# esp12e.net
KiCad netlist of a schematic drawn in EAGLE
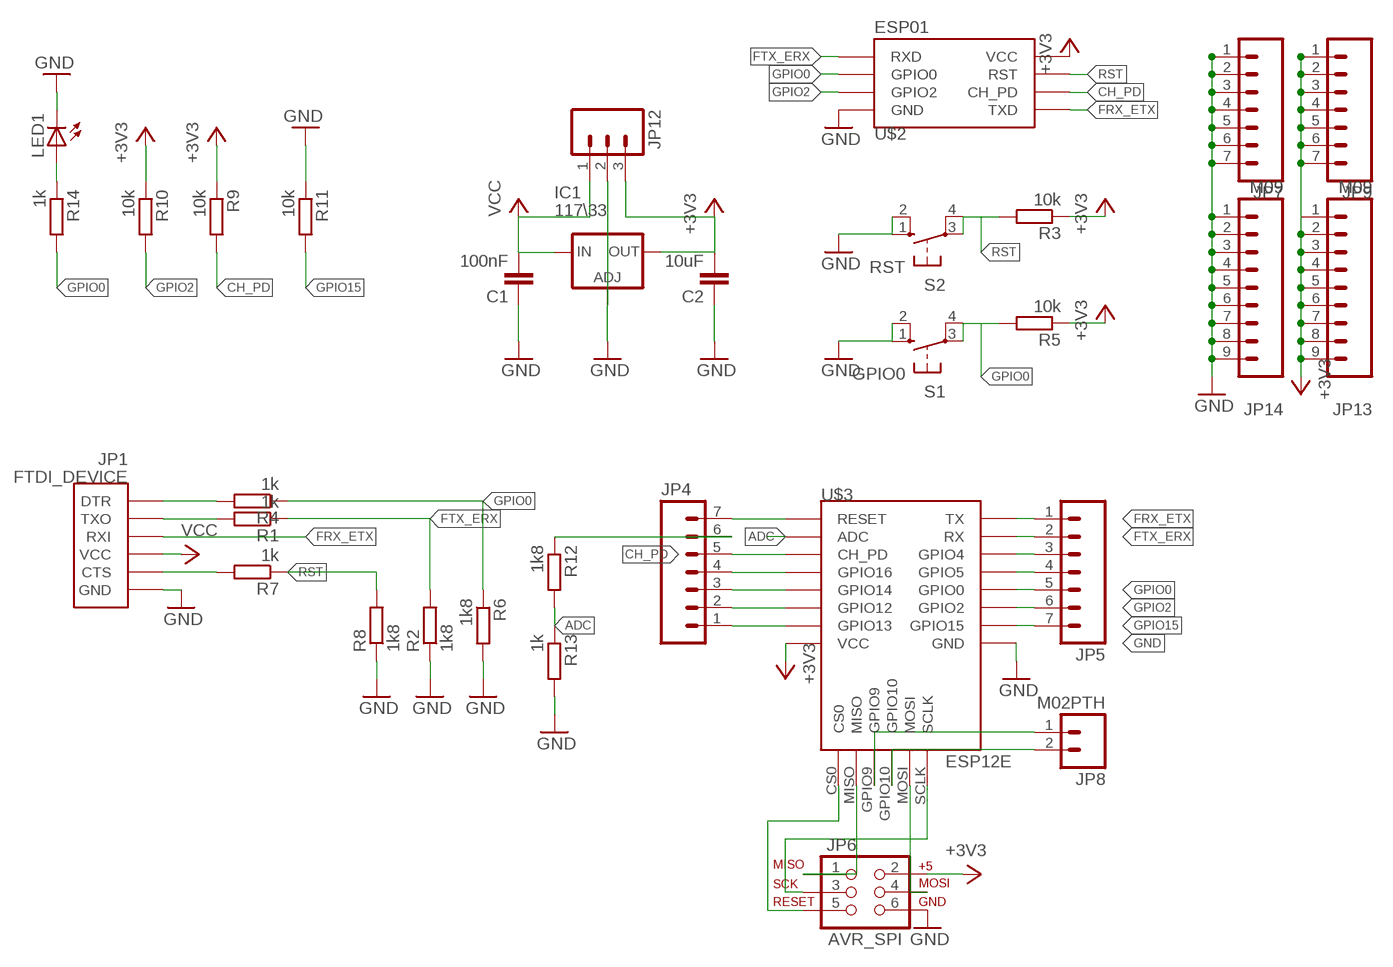
[diagram p0: schematic, sheet 1]

(export (version "E")
  (design (tool "Eeschema 10.0.6"))
  (components
    (comp (ref "C1")
      (value "100nF")
      (footprint "eagle-import:C1206")
      (libsource (lib "eagle-import") (part "C-EUC1206"))
    )
    (comp (ref "C2")
      (value "10uF")
      (footprint "eagle-import:C1206")
      (libsource (lib "eagle-import") (part "C-EUC1206"))
    )
    (comp (ref "IC1")
      (value "117\\33")
      (footprint "eagle-import:SOT223")
      (libsource (lib "eagle-import") (part "LD117A?S33TR"))
    )
    (comp (ref "JP1")
      (value "FTDI_DEVICE")
      (footprint "eagle-import:FTDI_DEVICE_SIDE")
      (libsource (lib "eagle-import") (part "FTDI_DEVICE"))
    )
    (comp (ref "JP4")
      (value "M07")
      (footprint "eagle-import:1X07")
      (libsource (lib "eagle-import") (part "M07"))
    )
    (comp (ref "JP5")
      (value "M07")
      (footprint "eagle-import:1X07")
      (libsource (lib "eagle-import") (part "M07"))
    )
    (comp (ref "JP6")
      (value "AVR_SPI")
      (footprint "eagle-import:2X3-NS")
      (libsource (lib "eagle-import") (part "AVR_SPI_PRG_6NS"))
    )
    (comp (ref "JP7")
      (value "M07")
      (footprint "eagle-import:1X07")
      (libsource (lib "eagle-import") (part "M07"))
    )
    (comp (ref "JP8")
      (value "M02PTH")
      (footprint "eagle-import:1X02")
      (libsource (lib "eagle-import") (part "M02PTH"))
    )
    (comp (ref "JP9")
      (value "M07")
      (footprint "eagle-import:1X07")
      (libsource (lib "eagle-import") (part "M07"))
    )
    (comp (ref "JP12")
      (value "M03PTH")
      (footprint "eagle-import:1X03")
      (libsource (lib "eagle-import") (part "M03PTH"))
    )
    (comp (ref "JP13")
      (value "M09")
      (footprint "eagle-import:1X09")
      (libsource (lib "eagle-import") (part "M09"))
    )
    (comp (ref "JP14")
      (value "M09")
      (footprint "eagle-import:1X09")
      (libsource (lib "eagle-import") (part "M09"))
    )
    (comp (ref "LED1")
      (value "LEDSMT1206")
      (footprint "eagle-import:1206")
      (libsource (lib "eagle-import") (part "LEDSMT1206"))
    )
    (comp (ref "R1")
      (value "1k")
      (footprint "eagle-import:M1206")
      (libsource (lib "eagle-import") (part "R-EU_M1206"))
    )
    (comp (ref "R2")
      (value "1k8")
      (footprint "eagle-import:M1206")
      (libsource (lib "eagle-import") (part "R-EU_M1206"))
    )
    (comp (ref "R3")
      (value "10k")
      (footprint "eagle-import:M1206")
      (libsource (lib "eagle-import") (part "R-EU_M1206"))
    )
    (comp (ref "R4")
      (value "1k")
      (footprint "eagle-import:M1206")
      (libsource (lib "eagle-import") (part "R-EU_M1206"))
    )
    (comp (ref "R5")
      (value "10k")
      (footprint "eagle-import:M1206")
      (libsource (lib "eagle-import") (part "R-EU_M1206"))
    )
    (comp (ref "R6")
      (value "1k8")
      (footprint "eagle-import:M1206")
      (libsource (lib "eagle-import") (part "R-EU_M1206"))
    )
    (comp (ref "R7")
      (value "1k")
      (footprint "eagle-import:M1206")
      (libsource (lib "eagle-import") (part "R-EU_M1206"))
    )
    (comp (ref "R8")
      (value "1k8")
      (footprint "eagle-import:M1206")
      (libsource (lib "eagle-import") (part "R-EU_M1206"))
    )
    (comp (ref "R9")
      (value "10k")
      (footprint "eagle-import:M1206")
      (libsource (lib "eagle-import") (part "R-EU_M1206"))
    )
    (comp (ref "R10")
      (value "10k")
      (footprint "eagle-import:M1206")
      (libsource (lib "eagle-import") (part "R-EU_M1206"))
    )
    (comp (ref "R11")
      (value "10k")
      (footprint "eagle-import:M1206")
      (libsource (lib "eagle-import") (part "R-EU_M1206"))
    )
    (comp (ref "R12")
      (value "1k8")
      (footprint "eagle-import:M1206")
      (libsource (lib "eagle-import") (part "R-EU_M1206"))
    )
    (comp (ref "R13")
      (value "1k")
      (footprint "eagle-import:M1206")
      (libsource (lib "eagle-import") (part "R-EU_M1206"))
    )
    (comp (ref "R14")
      (value "1k")
      (footprint "eagle-import:M1206")
      (libsource (lib "eagle-import") (part "R-EU_M1206"))
    )
    (comp (ref "S1")
      (value "GPIO0")
      (footprint "eagle-import:B3F-10XX")
      (fields (field (name "MPN") "B3F-1000"))
      (libsource (lib "eagle-import") (part "10-XX"))
    )
    (comp (ref "S2")
      (value "RST")
      (footprint "eagle-import:B3F-10XX")
      (fields (field (name "MPN") "B3F-1000"))
      (libsource (lib "eagle-import") (part "10-XX"))
    )
    (comp (ref "U$2")
      (value "ESP01")
      (footprint "eagle-import:ESP01")
      (libsource (lib "eagle-import") (part "ESP01"))
    )
    (comp (ref "U$3")
      (value "ESP12E")
      (footprint "eagle-import:ESP12E")
      (libsource (lib "eagle-import") (part "ESP12E"))
    )
  )
  (nets
    (net (code "1") (name "+3V3") (class "Default")
      (node (ref "C2") (pin "2") (pinfunction "2_2") (pintype "passive"))
      (node (ref "IC1") (pin "4") (pinfunction "OUT_4") (pintype "passive"))
      (node (ref "JP12") (pin "3") (pinfunction "3_3") (pintype "passive"))
      (node (ref "JP13") (pin "1") (pinfunction "1_1") (pintype "passive"))
      (node (ref "JP13") (pin "2") (pinfunction "2_2") (pintype "passive"))
      (node (ref "JP13") (pin "3") (pinfunction "3_3") (pintype "passive"))
      (node (ref "JP13") (pin "4") (pinfunction "4_4") (pintype "passive"))
      (node (ref "JP13") (pin "5") (pinfunction "5_5") (pintype "passive"))
      (node (ref "JP13") (pin "6") (pinfunction "6_6") (pintype "passive"))
      (node (ref "JP13") (pin "7") (pinfunction "7_7") (pintype "passive"))
      (node (ref "JP13") (pin "8") (pinfunction "8_8") (pintype "passive"))
      (node (ref "JP13") (pin "9") (pinfunction "9_9") (pintype "passive"))
      (node (ref "JP6") (pin "2") (pinfunction "2_2") (pintype "passive"))
      (node (ref "JP9") (pin "1") (pinfunction "1_1") (pintype "passive"))
      (node (ref "JP9") (pin "2") (pinfunction "2_2") (pintype "passive"))
      (node (ref "JP9") (pin "3") (pinfunction "3_3") (pintype "passive"))
      (node (ref "JP9") (pin "4") (pinfunction "4_4") (pintype "passive"))
      (node (ref "JP9") (pin "5") (pinfunction "5_5") (pintype "passive"))
      (node (ref "JP9") (pin "6") (pinfunction "6_6") (pintype "passive"))
      (node (ref "JP9") (pin "7") (pinfunction "7_7") (pintype "passive"))
      (node (ref "R10") (pin "1") (pinfunction "1_1") (pintype "passive"))
      (node (ref "R3") (pin "1") (pinfunction "1_1") (pintype "passive"))
      (node (ref "R5") (pin "1") (pinfunction "1_1") (pintype "passive"))
      (node (ref "R9") (pin "1") (pinfunction "1_1") (pintype "passive"))
      (node (ref "U$2") (pin "VCC") (pinfunction "VCC_VCC") (pintype "bidirectional"))
      (node (ref "U$3") (pin "VCC") (pinfunction "VCC_VCC") (pintype "bidirectional"))
    )
    (net (code "2") (name "ADC") (class "Default")
      (node (ref "R12") (pin "2") (pinfunction "2_2") (pintype "passive"))
      (node (ref "R13") (pin "1") (pinfunction "1_1") (pintype "passive"))
      (node (ref "U$3") (pin "ADC") (pinfunction "ADC_ADC") (pintype "bidirectional"))
    )
    (net (code "3") (name "CH_PD") (class "Default")
      (node (ref "JP4") (pin "5") (pinfunction "5_5") (pintype "passive"))
      (node (ref "R9") (pin "2") (pinfunction "2_2") (pintype "passive"))
      (node (ref "U$2") (pin "CH_PD") (pinfunction "CH_PD_CH_PD") (pintype "bidirectional"))
      (node (ref "U$3") (pin "CH_PD") (pinfunction "CH_PD_CH_PD") (pintype "bidirectional"))
    )
    (net (code "4") (name "FRX_ETX") (class "Default")
      (node (ref "JP1") (pin "P$3") (pinfunction "RXI_P$3") (pintype "bidirectional"))
      (node (ref "JP5") (pin "1") (pinfunction "1_1") (pintype "passive"))
      (node (ref "U$2") (pin "TX") (pinfunction "TXD_TX") (pintype "bidirectional"))
      (node (ref "U$3") (pin "TX") (pinfunction "TX_TX") (pintype "bidirectional"))
    )
    (net (code "5") (name "FTX_ERX") (class "Default")
      (node (ref "JP5") (pin "2") (pinfunction "2_2") (pintype "passive"))
      (node (ref "R1") (pin "1") (pinfunction "1_1") (pintype "passive"))
      (node (ref "R2") (pin "2") (pinfunction "2_2") (pintype "passive"))
      (node (ref "U$2") (pin "RX") (pinfunction "RXD_RX") (pintype "bidirectional"))
      (node (ref "U$3") (pin "RX") (pinfunction "RX_RX") (pintype "bidirectional"))
    )
    (net (code "6") (name "GND") (class "Default")
      (node (ref "C1") (pin "1") (pinfunction "1_1") (pintype "passive"))
      (node (ref "C2") (pin "1") (pinfunction "1_1") (pintype "passive"))
      (node (ref "IC1") (pin "1") (pinfunction "ADJ_1") (pintype "input"))
      (node (ref "JP1") (pin "P$6") (pinfunction "GND_P$6") (pintype "bidirectional"))
      (node (ref "JP12") (pin "2") (pinfunction "2_2") (pintype "passive"))
      (node (ref "JP14") (pin "1") (pinfunction "1_1") (pintype "passive"))
      (node (ref "JP14") (pin "2") (pinfunction "2_2") (pintype "passive"))
      (node (ref "JP14") (pin "3") (pinfunction "3_3") (pintype "passive"))
      (node (ref "JP14") (pin "4") (pinfunction "4_4") (pintype "passive"))
      (node (ref "JP14") (pin "5") (pinfunction "5_5") (pintype "passive"))
      (node (ref "JP14") (pin "6") (pinfunction "6_6") (pintype "passive"))
      (node (ref "JP14") (pin "7") (pinfunction "7_7") (pintype "passive"))
      (node (ref "JP14") (pin "8") (pinfunction "8_8") (pintype "passive"))
      (node (ref "JP14") (pin "9") (pinfunction "9_9") (pintype "passive"))
      (node (ref "JP6") (pin "6") (pinfunction "6_6") (pintype "passive"))
      (node (ref "JP7") (pin "1") (pinfunction "1_1") (pintype "passive"))
      (node (ref "JP7") (pin "2") (pinfunction "2_2") (pintype "passive"))
      (node (ref "JP7") (pin "3") (pinfunction "3_3") (pintype "passive"))
      (node (ref "JP7") (pin "4") (pinfunction "4_4") (pintype "passive"))
      (node (ref "JP7") (pin "5") (pinfunction "5_5") (pintype "passive"))
      (node (ref "JP7") (pin "6") (pinfunction "6_6") (pintype "passive"))
      (node (ref "JP7") (pin "7") (pinfunction "7_7") (pintype "passive"))
      (node (ref "LED1") (pin "C") (pinfunction "C_C") (pintype "passive"))
      (node (ref "R11") (pin "1") (pinfunction "1_1") (pintype "passive"))
      (node (ref "R13") (pin "2") (pinfunction "2_2") (pintype "passive"))
      (node (ref "R2") (pin "1") (pinfunction "1_1") (pintype "passive"))
      (node (ref "R6") (pin "2") (pinfunction "2_2") (pintype "passive"))
      (node (ref "R8") (pin "1") (pinfunction "1_1") (pintype "passive"))
      (node (ref "S1") (pin "1") (pinfunction "S_1") (pintype "passive"))
      (node (ref "S1") (pin "2") (pinfunction "S1_2") (pintype "passive"))
      (node (ref "S2") (pin "1") (pinfunction "S_1") (pintype "passive"))
      (node (ref "S2") (pin "2") (pinfunction "S1_2") (pintype "passive"))
      (node (ref "U$2") (pin "GND") (pinfunction "GND_GND") (pintype "bidirectional"))
      (node (ref "U$3") (pin "GND") (pinfunction "GND_GND") (pintype "bidirectional"))
    )
    (net (code "7") (name "GPIO0") (class "Default")
      (node (ref "JP5") (pin "5") (pinfunction "5_5") (pintype "passive"))
      (node (ref "R14") (pin "2") (pinfunction "2_2") (pintype "passive"))
      (node (ref "R4") (pin "1") (pinfunction "1_1") (pintype "passive"))
      (node (ref "R5") (pin "2") (pinfunction "2_2") (pintype "passive"))
      (node (ref "R6") (pin "1") (pinfunction "1_1") (pintype "passive"))
      (node (ref "S1") (pin "3") (pinfunction "P_3") (pintype "passive"))
      (node (ref "S1") (pin "4") (pinfunction "P1_4") (pintype "passive"))
      (node (ref "U$2") (pin "GPIO0") (pinfunction "GPIO0_GPIO0") (pintype "bidirectional"))
      (node (ref "U$3") (pin "GPIO0") (pinfunction "GPIO0_GPIO0") (pintype "bidirectional"))
    )
    (net (code "8") (name "GPIO2") (class "Default")
      (node (ref "JP5") (pin "6") (pinfunction "6_6") (pintype "passive"))
      (node (ref "R10") (pin "2") (pinfunction "2_2") (pintype "passive"))
      (node (ref "U$2") (pin "GPIO2") (pinfunction "GPIO2_GPIO2") (pintype "bidirectional"))
      (node (ref "U$3") (pin "GPIO2") (pinfunction "GPIO2_GPIO2") (pintype "bidirectional"))
    )
    (net (code "9") (name "GPIO15") (class "Default")
      (node (ref "JP5") (pin "7") (pinfunction "7_7") (pintype "passive"))
      (node (ref "R11") (pin "2") (pinfunction "2_2") (pintype "passive"))
      (node (ref "U$3") (pin "GPIO15") (pinfunction "GPIO15_GPIO15") (pintype "bidirectional"))
    )
    (net (code "10") (name "Net-(JP1-CTS)") (class "Default")
      (node (ref "JP1") (pin "P$5") (pinfunction "CTS_P$5") (pintype "bidirectional"))
      (node (ref "R7") (pin "2") (pinfunction "2_2") (pintype "passive"))
    )
    (net (code "11") (name "Net-(JP1-DTR)") (class "Default")
      (node (ref "JP1") (pin "P$1") (pinfunction "DTR_P$1") (pintype "bidirectional"))
      (node (ref "R4") (pin "2") (pinfunction "2_2") (pintype "passive"))
    )
    (net (code "12") (name "Net-(JP1-TXO)") (class "Default")
      (node (ref "JP1") (pin "P$2") (pinfunction "TXO_P$2") (pintype "bidirectional"))
      (node (ref "R1") (pin "2") (pinfunction "2_2") (pintype "passive"))
    )
    (net (code "13") (name "Net-(JP4-Pad1)") (class "Default")
      (node (ref "JP4") (pin "1") (pinfunction "1_1") (pintype "passive"))
      (node (ref "U$3") (pin "GPIO13") (pinfunction "GPIO13_GPIO13") (pintype "bidirectional"))
    )
    (net (code "14") (name "Net-(JP4-Pad2)") (class "Default")
      (node (ref "JP4") (pin "2") (pinfunction "2_2") (pintype "passive"))
      (node (ref "U$3") (pin "GPIO12") (pinfunction "GPIO12_GPIO12") (pintype "bidirectional"))
    )
    (net (code "15") (name "Net-(JP4-Pad3)") (class "Default")
      (node (ref "JP4") (pin "3") (pinfunction "3_3") (pintype "passive"))
      (node (ref "U$3") (pin "GPIO14") (pinfunction "GPIO14_GPIO14") (pintype "bidirectional"))
    )
    (net (code "16") (name "Net-(JP4-Pad4)") (class "Default")
      (node (ref "JP4") (pin "4") (pinfunction "4_4") (pintype "passive"))
      (node (ref "U$3") (pin "GPIO16") (pinfunction "GPIO16_GPIO16") (pintype "bidirectional"))
    )
    (net (code "17") (name "Net-(JP4-Pad6)") (class "Default")
      (node (ref "JP4") (pin "6") (pinfunction "6_6") (pintype "passive"))
      (node (ref "R12") (pin "1") (pinfunction "1_1") (pintype "passive"))
    )
    (net (code "18") (name "Net-(JP5-Pad3)") (class "Default")
      (node (ref "JP5") (pin "3") (pinfunction "3_3") (pintype "passive"))
      (node (ref "U$3") (pin "GPIO4") (pinfunction "GPIO4_GPIO4") (pintype "bidirectional"))
    )
    (net (code "19") (name "Net-(JP5-Pad4)") (class "Default")
      (node (ref "JP5") (pin "4") (pinfunction "4_4") (pintype "passive"))
      (node (ref "U$3") (pin "GPIO5") (pinfunction "GPIO5_GPIO5") (pintype "bidirectional"))
    )
    (net (code "20") (name "Net-(JP6-Pad1)") (class "Default")
      (node (ref "JP6") (pin "1") (pinfunction "1_1") (pintype "passive"))
      (node (ref "U$3") (pin "MISO") (pinfunction "MISO_MISO") (pintype "bidirectional"))
    )
    (net (code "21") (name "Net-(JP6-Pad3)") (class "Default")
      (node (ref "JP6") (pin "3") (pinfunction "3_3") (pintype "passive"))
      (node (ref "U$3") (pin "SCLK") (pinfunction "SCLK_SCLK") (pintype "bidirectional"))
    )
    (net (code "22") (name "Net-(JP6-Pad4)") (class "Default")
      (node (ref "JP6") (pin "4") (pinfunction "4_4") (pintype "passive"))
      (node (ref "U$3") (pin "MOSI") (pinfunction "MOSI_MOSI") (pintype "bidirectional"))
    )
    (net (code "23") (name "Net-(JP6-Pad5)") (class "Default")
      (node (ref "JP6") (pin "5") (pinfunction "5_5") (pintype "passive"))
      (node (ref "U$3") (pin "CS0") (pinfunction "CS0_CS0") (pintype "bidirectional"))
    )
    (net (code "24") (name "Net-(JP8-Pad1)") (class "Default")
      (node (ref "JP8") (pin "1") (pinfunction "1_1") (pintype "passive"))
      (node (ref "U$3") (pin "GPIO9") (pinfunction "GPIO9_GPIO9") (pintype "bidirectional"))
    )
    (net (code "25") (name "Net-(JP8-Pad2)") (class "Default")
      (node (ref "JP8") (pin "2") (pinfunction "2_2") (pintype "passive"))
      (node (ref "U$3") (pin "GPIO10") (pinfunction "GPIO10_GPIO10") (pintype "bidirectional"))
    )
    (net (code "26") (name "Net-(LED1-PadA)") (class "Default")
      (node (ref "LED1") (pin "A") (pinfunction "A_A") (pintype "passive"))
      (node (ref "R14") (pin "1") (pinfunction "1_1") (pintype "passive"))
    )
    (net (code "27") (name "RST") (class "Default")
      (node (ref "JP4") (pin "7") (pinfunction "7_7") (pintype "passive"))
      (node (ref "R3") (pin "2") (pinfunction "2_2") (pintype "passive"))
      (node (ref "R7") (pin "1") (pinfunction "1_1") (pintype "passive"))
      (node (ref "R8") (pin "2") (pinfunction "2_2") (pintype "passive"))
      (node (ref "S2") (pin "3") (pinfunction "P_3") (pintype "passive"))
      (node (ref "S2") (pin "4") (pinfunction "P1_4") (pintype "passive"))
      (node (ref "U$2") (pin "RST") (pinfunction "RST_RST") (pintype "bidirectional"))
      (node (ref "U$3") (pin "RESET") (pinfunction "RESET_RESET") (pintype "bidirectional"))
    )
    (net (code "28") (name "VCC") (class "Default")
      (node (ref "C1") (pin "2") (pinfunction "2_2") (pintype "passive"))
      (node (ref "IC1") (pin "3") (pinfunction "IN_3") (pintype "input"))
      (node (ref "JP1") (pin "P$4") (pinfunction "VCC_P$4") (pintype "bidirectional"))
      (node (ref "JP12") (pin "1") (pinfunction "1_1") (pintype "passive"))
    )
  )
)
